# PPS1_schemas_V2.net
KiCad netlist of a schematic drawn in EAGLE
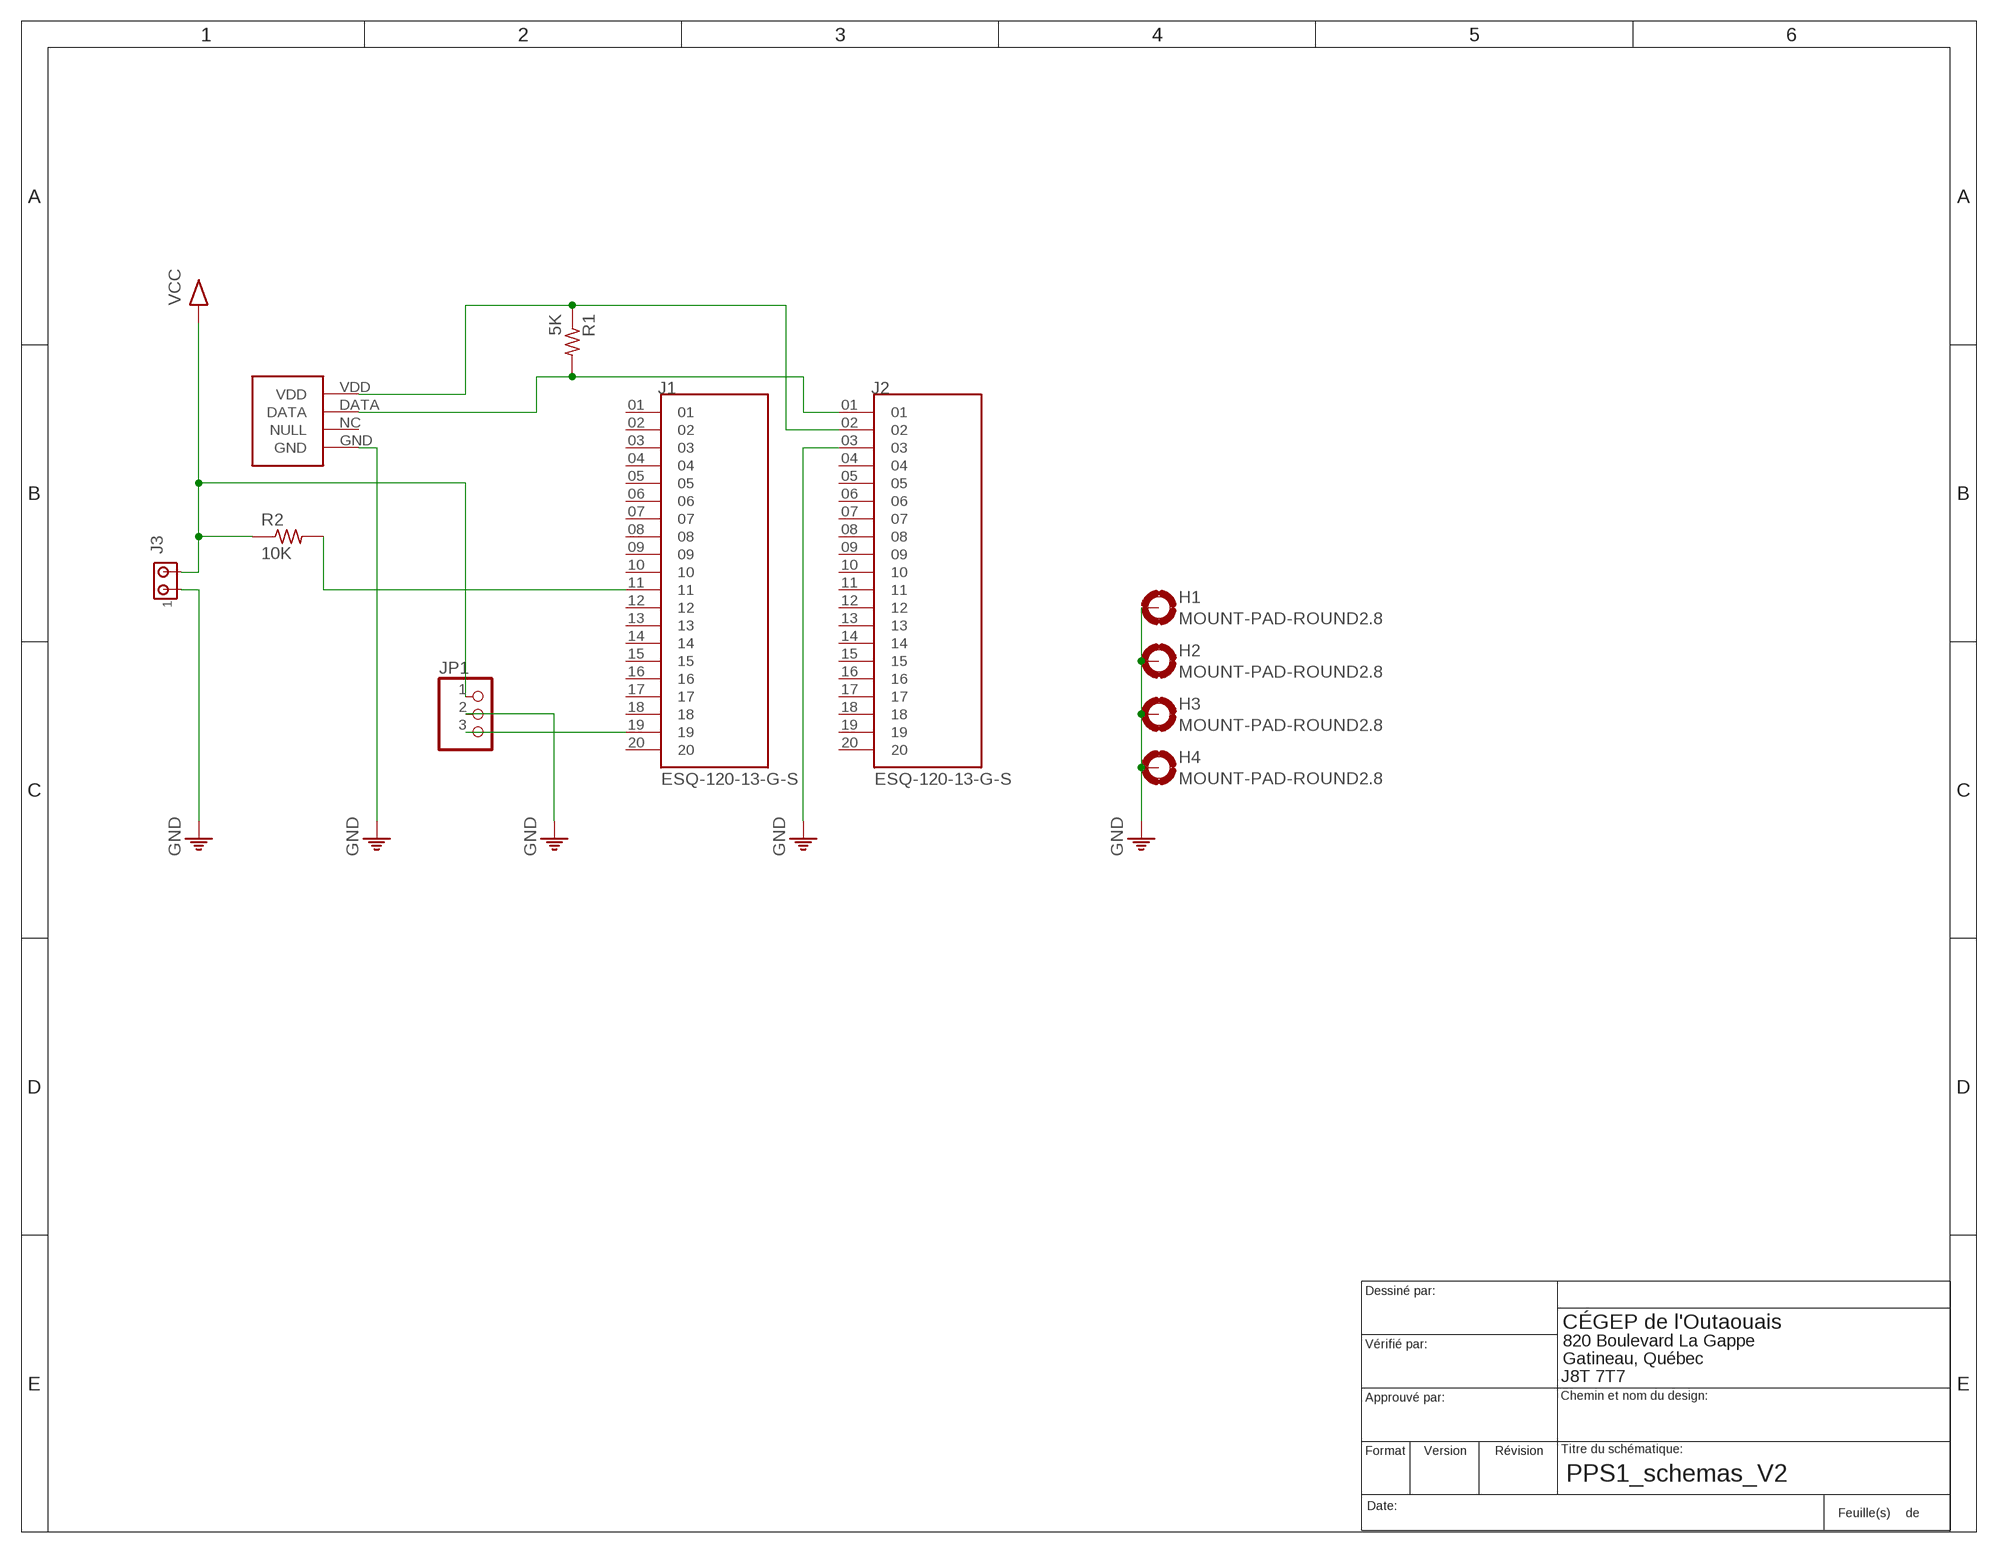
[diagram p0: schematic, sheet 1]

(export (version "E")
  (design (tool "Eeschema 10.0.6"))
  (components
    (comp (ref "H1")
      (value "MOUNT-PAD-ROUND2.8")
      (footprint "eagle-import:2,8-PAD")
      (libsource (lib "eagle-import") (part "MOUNT-PAD-ROUND2.8"))
    )
    (comp (ref "H2")
      (value "MOUNT-PAD-ROUND2.8")
      (footprint "eagle-import:2,8-PAD")
      (libsource (lib "eagle-import") (part "MOUNT-PAD-ROUND2.8"))
    )
    (comp (ref "H3")
      (value "MOUNT-PAD-ROUND2.8")
      (footprint "eagle-import:2,8-PAD")
      (libsource (lib "eagle-import") (part "MOUNT-PAD-ROUND2.8"))
    )
    (comp (ref "H4")
      (value "MOUNT-PAD-ROUND2.8")
      (footprint "eagle-import:2,8-PAD")
      (libsource (lib "eagle-import") (part "MOUNT-PAD-ROUND2.8"))
    )
    (comp (ref "J1")
      (value "ESQ-120-13-G-S")
      (footprint "eagle-import:SAMTEC_ESQ-120-13-G-S")
      (fields (field (name "MF") "Samtec"))
      (libsource (lib "eagle-import") (part "ESQ-120-13-G-S"))
    )
    (comp (ref "J2")
      (value "ESQ-120-13-G-S")
      (footprint "eagle-import:SAMTEC_ESQ-120-13-G-S")
      (fields (field (name "MF") "Samtec"))
      (libsource (lib "eagle-import") (part "ESQ-120-13-G-S"))
    )
    (comp (ref "J3")
      (value "MTA02-100")
      (footprint "eagle-import:10X02MTA")
      (libsource (lib "eagle-import") (part "MTA02-100"))
    )
    (comp (ref "JP1")
      (value "PINHD-1X3")
      (footprint "eagle-import:1X03")
      (libsource (lib "eagle-import") (part "PINHD-1X3"))
    )
    (comp (ref "R1")
      (value "5K")
      (footprint "eagle-import:M1206")
      (libsource (lib "eagle-import") (part "RM1206"))
    )
    (comp (ref "R2")
      (value "10K")
      (footprint "eagle-import:M1206")
      (libsource (lib "eagle-import") (part "RM1206"))
    )
    (comp (ref "U$1")
      (value "DHT22")
      (footprint "eagle-import:DHT22")
      (fields (field (name "MF") "Aosong Electronics"))
      (libsource (lib "eagle-import") (part "DHT22"))
    )
  )
  (nets
    (net (code "1") (name "GND") (class "Default")
      (node (ref "H1") (pin "B2,8") (pinfunction "MOUNT_B2,8") (pintype "passive"))
      (node (ref "H2") (pin "B2,8") (pinfunction "MOUNT_B2,8") (pintype "passive"))
      (node (ref "H3") (pin "B2,8") (pinfunction "MOUNT_B2,8") (pintype "passive"))
      (node (ref "H4") (pin "B2,8") (pinfunction "MOUNT_B2,8") (pintype "passive"))
      (node (ref "J2") (pin "03") (pinfunction "03_03") (pintype "passive"))
      (node (ref "J3") (pin "1") (pinfunction "1_1") (pintype "passive"))
      (node (ref "JP1") (pin "2") (pinfunction "2_2") (pintype "passive"))
      (node (ref "U$1") (pin "GND") (pinfunction "GND_GND") (pintype "power_in"))
    )
    (net (code "2") (name "Net-(J1-Pad11)") (class "Default")
      (node (ref "J1") (pin "11") (pinfunction "11_11") (pintype "passive"))
      (node (ref "R2") (pin "2") (pinfunction "2_2") (pintype "passive"))
    )
    (net (code "3") (name "Net-(J1-Pad19)") (class "Default")
      (node (ref "J1") (pin "19") (pinfunction "19_19") (pintype "passive"))
      (node (ref "JP1") (pin "3") (pinfunction "3_3") (pintype "passive"))
    )
    (net (code "4") (name "Net-(J2-Pad01)") (class "Default")
      (node (ref "J2") (pin "01") (pinfunction "01_01") (pintype "passive"))
      (node (ref "R1") (pin "2") (pinfunction "2_2") (pintype "passive"))
      (node (ref "U$1") (pin "DATA") (pinfunction "DATA_DATA") (pintype "output"))
    )
    (net (code "5") (name "Net-(J2-Pad02)") (class "Default")
      (node (ref "J2") (pin "02") (pinfunction "02_02") (pintype "passive"))
      (node (ref "R1") (pin "1") (pinfunction "1_1") (pintype "passive"))
      (node (ref "U$1") (pin "VDD") (pinfunction "VDD_VDD") (pintype "power_in"))
    )
    (net (code "6") (name "VCC") (class "Default")
      (node (ref "J3") (pin "2") (pinfunction "2_2") (pintype "passive"))
      (node (ref "JP1") (pin "1") (pinfunction "1_1") (pintype "passive"))
      (node (ref "R2") (pin "1") (pinfunction "1_1") (pintype "passive"))
    )
    (net (code "7") (name "unconnected-(J1-Pad01)") (class "Default")
      (node (ref "J1") (pin "01") (pinfunction "01_01") (pintype "passive"))
    )
    (net (code "8") (name "unconnected-(J1-Pad02)") (class "Default")
      (node (ref "J1") (pin "02") (pinfunction "02_02") (pintype "passive"))
    )
    (net (code "9") (name "unconnected-(J1-Pad03)") (class "Default")
      (node (ref "J1") (pin "03") (pinfunction "03_03") (pintype "passive"))
    )
    (net (code "10") (name "unconnected-(J1-Pad04)") (class "Default")
      (node (ref "J1") (pin "04") (pinfunction "04_04") (pintype "passive"))
    )
    (net (code "11") (name "unconnected-(J1-Pad05)") (class "Default")
      (node (ref "J1") (pin "05") (pinfunction "05_05") (pintype "passive"))
    )
    (net (code "12") (name "unconnected-(J1-Pad06)") (class "Default")
      (node (ref "J1") (pin "06") (pinfunction "06_06") (pintype "passive"))
    )
    (net (code "13") (name "unconnected-(J1-Pad07)") (class "Default")
      (node (ref "J1") (pin "07") (pinfunction "07_07") (pintype "passive"))
    )
    (net (code "14") (name "unconnected-(J1-Pad08)") (class "Default")
      (node (ref "J1") (pin "08") (pinfunction "08_08") (pintype "passive"))
    )
    (net (code "15") (name "unconnected-(J1-Pad09)") (class "Default")
      (node (ref "J1") (pin "09") (pinfunction "09_09") (pintype "passive"))
    )
    (net (code "16") (name "unconnected-(J1-Pad10)") (class "Default")
      (node (ref "J1") (pin "10") (pinfunction "10_10") (pintype "passive"))
    )
    (net (code "17") (name "unconnected-(J1-Pad12)") (class "Default")
      (node (ref "J1") (pin "12") (pinfunction "12_12") (pintype "passive"))
    )
    (net (code "18") (name "unconnected-(J1-Pad13)") (class "Default")
      (node (ref "J1") (pin "13") (pinfunction "13_13") (pintype "passive"))
    )
    (net (code "19") (name "unconnected-(J1-Pad14)") (class "Default")
      (node (ref "J1") (pin "14") (pinfunction "14_14") (pintype "passive"))
    )
    (net (code "20") (name "unconnected-(J1-Pad15)") (class "Default")
      (node (ref "J1") (pin "15") (pinfunction "15_15") (pintype "passive"))
    )
    (net (code "21") (name "unconnected-(J1-Pad16)") (class "Default")
      (node (ref "J1") (pin "16") (pinfunction "16_16") (pintype "passive"))
    )
    (net (code "22") (name "unconnected-(J1-Pad17)") (class "Default")
      (node (ref "J1") (pin "17") (pinfunction "17_17") (pintype "passive"))
    )
    (net (code "23") (name "unconnected-(J1-Pad18)") (class "Default")
      (node (ref "J1") (pin "18") (pinfunction "18_18") (pintype "passive"))
    )
    (net (code "24") (name "unconnected-(J1-Pad20)") (class "Default")
      (node (ref "J1") (pin "20") (pinfunction "20_20") (pintype "passive"))
    )
    (net (code "25") (name "unconnected-(J2-Pad04)") (class "Default")
      (node (ref "J2") (pin "04") (pinfunction "04_04") (pintype "passive"))
    )
    (net (code "26") (name "unconnected-(J2-Pad05)") (class "Default")
      (node (ref "J2") (pin "05") (pinfunction "05_05") (pintype "passive"))
    )
    (net (code "27") (name "unconnected-(J2-Pad06)") (class "Default")
      (node (ref "J2") (pin "06") (pinfunction "06_06") (pintype "passive"))
    )
    (net (code "28") (name "unconnected-(J2-Pad07)") (class "Default")
      (node (ref "J2") (pin "07") (pinfunction "07_07") (pintype "passive"))
    )
    (net (code "29") (name "unconnected-(J2-Pad08)") (class "Default")
      (node (ref "J2") (pin "08") (pinfunction "08_08") (pintype "passive"))
    )
    (net (code "30") (name "unconnected-(J2-Pad09)") (class "Default")
      (node (ref "J2") (pin "09") (pinfunction "09_09") (pintype "passive"))
    )
    (net (code "31") (name "unconnected-(J2-Pad10)") (class "Default")
      (node (ref "J2") (pin "10") (pinfunction "10_10") (pintype "passive"))
    )
    (net (code "32") (name "unconnected-(J2-Pad11)") (class "Default")
      (node (ref "J2") (pin "11") (pinfunction "11_11") (pintype "passive"))
    )
    (net (code "33") (name "unconnected-(J2-Pad12)") (class "Default")
      (node (ref "J2") (pin "12") (pinfunction "12_12") (pintype "passive"))
    )
    (net (code "34") (name "unconnected-(J2-Pad13)") (class "Default")
      (node (ref "J2") (pin "13") (pinfunction "13_13") (pintype "passive"))
    )
    (net (code "35") (name "unconnected-(J2-Pad14)") (class "Default")
      (node (ref "J2") (pin "14") (pinfunction "14_14") (pintype "passive"))
    )
    (net (code "36") (name "unconnected-(J2-Pad15)") (class "Default")
      (node (ref "J2") (pin "15") (pinfunction "15_15") (pintype "passive"))
    )
    (net (code "37") (name "unconnected-(J2-Pad16)") (class "Default")
      (node (ref "J2") (pin "16") (pinfunction "16_16") (pintype "passive"))
    )
    (net (code "38") (name "unconnected-(J2-Pad17)") (class "Default")
      (node (ref "J2") (pin "17") (pinfunction "17_17") (pintype "passive"))
    )
    (net (code "39") (name "unconnected-(J2-Pad18)") (class "Default")
      (node (ref "J2") (pin "18") (pinfunction "18_18") (pintype "passive"))
    )
    (net (code "40") (name "unconnected-(J2-Pad19)") (class "Default")
      (node (ref "J2") (pin "19") (pinfunction "19_19") (pintype "passive"))
    )
    (net (code "41") (name "unconnected-(J2-Pad20)") (class "Default")
      (node (ref "J2") (pin "20") (pinfunction "20_20") (pintype "passive"))
    )
    (net (code "42") (name "unconnected-(U$1-NULL-PadNC)") (class "Default")
      (node (ref "U$1") (pin "NC") (pinfunction "NULL_NC") (pintype "no_connect"))
    )
  )
)
